# PhotonThingyStick.net
KiCad netlist of a schematic drawn in EAGLE
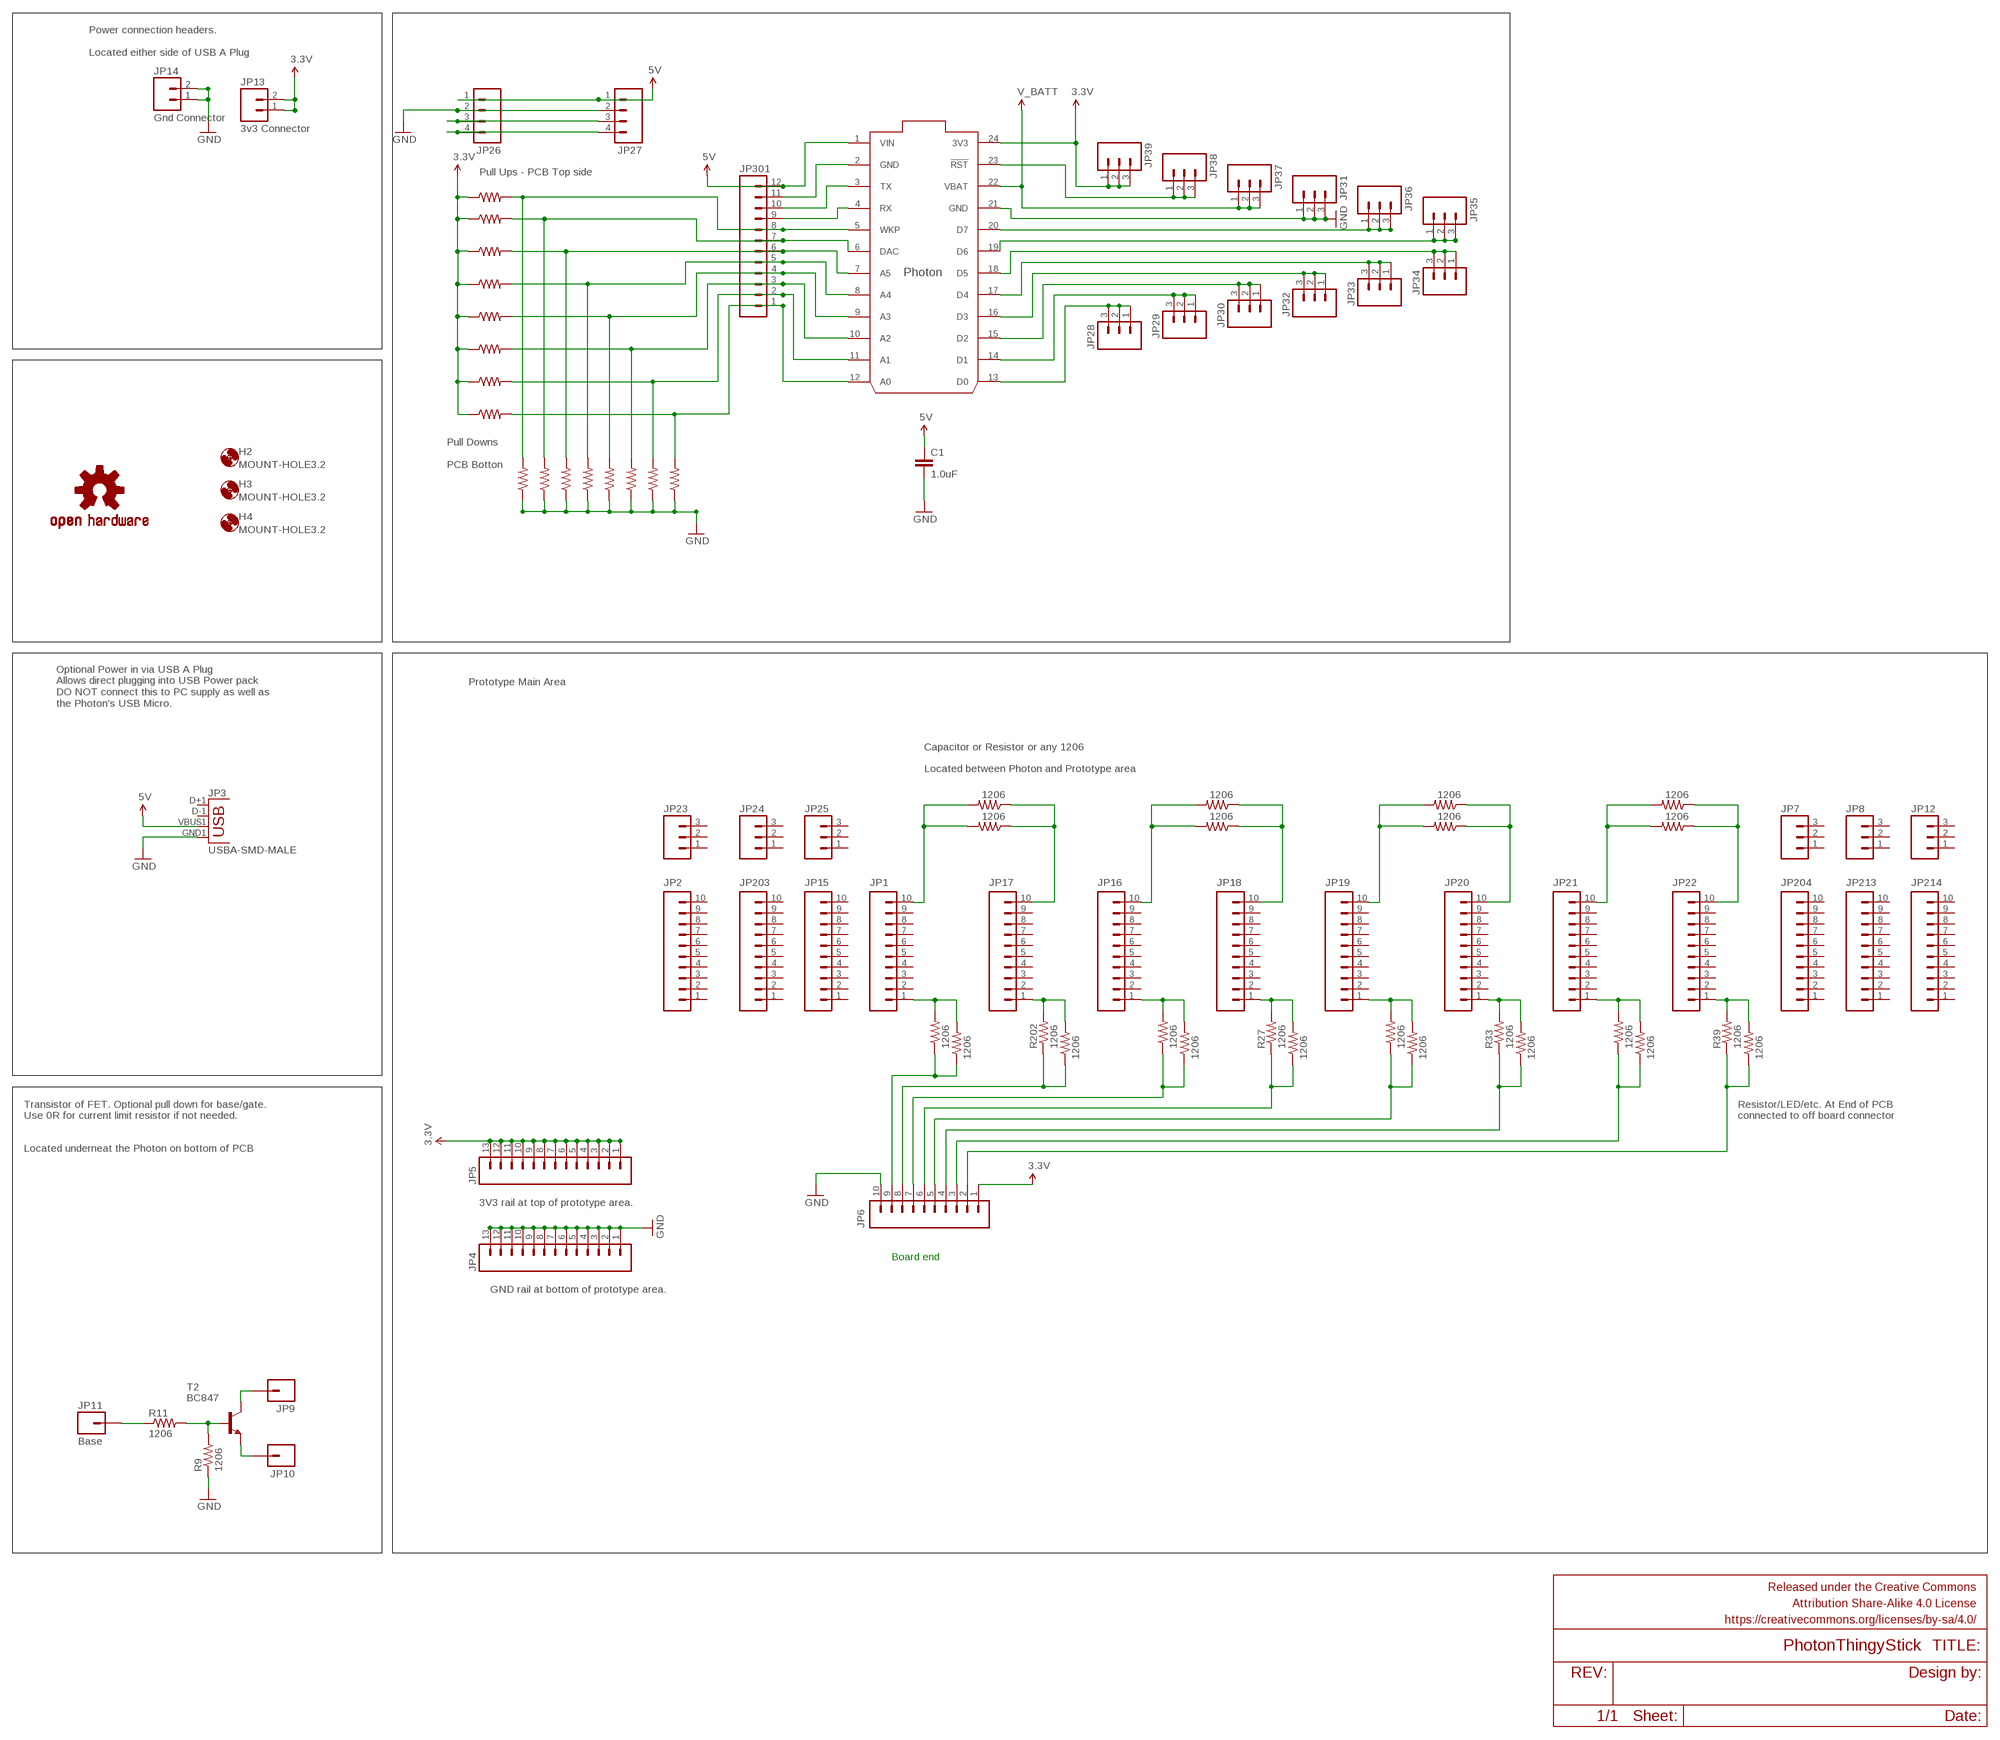
[diagram p0: schematic, sheet 1]

(export (version "E")
  (design (tool "Eeschema 10.0.6"))
  (components
    (comp (ref "C1")
      (value "1.0uF")
      (footprint "eagle-import:0805-CAP")
      (libsource (lib "eagle-import") (part "1.0UF-25V-+80/-20(0805){dblquote}"))
    )
    (comp (ref "FRAME1")
      (value "FRAME-LEDGER")
      (footprint "eagle-import:CREATIVE_COMMONS")
      (libsource (lib "eagle-import") (part "FRAME-LEDGER"))
    )
    (comp (ref "H2")
      (value "MOUNT-HOLE3.2")
      (footprint "eagle-import:3,2")
      (libsource (lib "eagle-import") (part "MOUNT-HOLE3.2"))
    )
    (comp (ref "H3")
      (value "MOUNT-HOLE3.2")
      (footprint "eagle-import:3,2")
      (libsource (lib "eagle-import") (part "MOUNT-HOLE3.2"))
    )
    (comp (ref "H4")
      (value "MOUNT-HOLE3.2")
      (footprint "eagle-import:3,2")
      (libsource (lib "eagle-import") (part "MOUNT-HOLE3.2"))
    )
    (comp (ref "IC1")
      (value "PHOTON_WITH_HEADERS")
      (footprint "eagle-import:PHOTON")
      (libsource (lib "eagle-import") (part "PHOTON_WITH_HEADERS"))
    )
    (comp (ref "JP1")
      (value "M10NO_SILK_PTH_FEMALE")
      (footprint "eagle-import:1X10_NO_SILK")
      (libsource (lib "eagle-import") (part "M10NO_SILK_PTH_FEMALE"))
    )
    (comp (ref "JP2")
      (value "M10NO_SILK_PTH_FEMALE")
      (footprint "eagle-import:1X10_NO_SILK")
      (libsource (lib "eagle-import") (part "M10NO_SILK_PTH_FEMALE"))
    )
    (comp (ref "JP3")
      (value "USBA-SMD-MALE")
      (footprint "eagle-import:USB-A-SMT-MALE")
      (libsource (lib "eagle-import") (part "USBA-SMD-MALE"))
    )
    (comp (ref "JP4")
      (value "M13")
      (footprint "eagle-import:1X13")
      (libsource (lib "eagle-import") (part "M13"))
    )
    (comp (ref "JP5")
      (value "M13")
      (footprint "eagle-import:1X13")
      (libsource (lib "eagle-import") (part "M13"))
    )
    (comp (ref "JP6")
      (value "M10NO_SILK_PTH_FEMALE")
      (footprint "eagle-import:1X10_NO_SILK")
      (libsource (lib "eagle-import") (part "M10NO_SILK_PTH_FEMALE"))
    )
    (comp (ref "JP7")
      (value "M031X03_NO_SILK")
      (footprint "eagle-import:1X03_NO_SILK")
      (libsource (lib "eagle-import") (part "M031X03_NO_SILK"))
    )
    (comp (ref "JP8")
      (value "M031X03_NO_SILK")
      (footprint "eagle-import:1X03_NO_SILK")
      (libsource (lib "eagle-import") (part "M031X03_NO_SILK"))
    )
    (comp (ref "JP9")
      (value "M01PTH")
      (footprint "eagle-import:1X01")
      (libsource (lib "eagle-import") (part "M01PTH"))
    )
    (comp (ref "JP10")
      (value "M01PTH")
      (footprint "eagle-import:1X01")
      (libsource (lib "eagle-import") (part "M01PTH"))
    )
    (comp (ref "JP11")
      (value "Base")
      (footprint "eagle-import:1X01")
      (libsource (lib "eagle-import") (part "M01PTH"))
    )
    (comp (ref "JP12")
      (value "M031X03_NO_SILK")
      (footprint "eagle-import:1X03_NO_SILK")
      (libsource (lib "eagle-import") (part "M031X03_NO_SILK"))
    )
    (comp (ref "JP13")
      (value "3v3 Connector")
      (footprint "eagle-import:1X02")
      (libsource (lib "eagle-import") (part "M02PTH"))
    )
    (comp (ref "JP14")
      (value "Gnd Connector")
      (footprint "eagle-import:1X02")
      (libsource (lib "eagle-import") (part "M02PTH"))
    )
    (comp (ref "JP15")
      (value "M10NO_SILK_PTH_FEMALE")
      (footprint "eagle-import:1X10_NO_SILK")
      (libsource (lib "eagle-import") (part "M10NO_SILK_PTH_FEMALE"))
    )
    (comp (ref "JP16")
      (value "M10NO_SILK_PTH_FEMALE")
      (footprint "eagle-import:1X10_NO_SILK")
      (libsource (lib "eagle-import") (part "M10NO_SILK_PTH_FEMALE"))
    )
    (comp (ref "JP17")
      (value "M10NO_SILK_PTH_FEMALE")
      (footprint "eagle-import:1X10_NO_SILK")
      (libsource (lib "eagle-import") (part "M10NO_SILK_PTH_FEMALE"))
    )
    (comp (ref "JP18")
      (value "M10NO_SILK_PTH_FEMALE")
      (footprint "eagle-import:1X10_NO_SILK")
      (libsource (lib "eagle-import") (part "M10NO_SILK_PTH_FEMALE"))
    )
    (comp (ref "JP19")
      (value "M10NO_SILK_PTH_FEMALE")
      (footprint "eagle-import:1X10_NO_SILK")
      (libsource (lib "eagle-import") (part "M10NO_SILK_PTH_FEMALE"))
    )
    (comp (ref "JP20")
      (value "M10NO_SILK_PTH_FEMALE")
      (footprint "eagle-import:1X10_NO_SILK")
      (libsource (lib "eagle-import") (part "M10NO_SILK_PTH_FEMALE"))
    )
    (comp (ref "JP21")
      (value "M10NO_SILK_PTH_FEMALE")
      (footprint "eagle-import:1X10_NO_SILK")
      (libsource (lib "eagle-import") (part "M10NO_SILK_PTH_FEMALE"))
    )
    (comp (ref "JP22")
      (value "M10NO_SILK_PTH_FEMALE")
      (footprint "eagle-import:1X10_NO_SILK")
      (libsource (lib "eagle-import") (part "M10NO_SILK_PTH_FEMALE"))
    )
    (comp (ref "JP23")
      (value "M031X03_NO_SILK")
      (footprint "eagle-import:1X03_NO_SILK")
      (libsource (lib "eagle-import") (part "M031X03_NO_SILK"))
    )
    (comp (ref "JP24")
      (value "M031X03_NO_SILK")
      (footprint "eagle-import:1X03_NO_SILK")
      (libsource (lib "eagle-import") (part "M031X03_NO_SILK"))
    )
    (comp (ref "JP25")
      (value "M031X03_NO_SILK")
      (footprint "eagle-import:1X03_NO_SILK")
      (libsource (lib "eagle-import") (part "M031X03_NO_SILK"))
    )
    (comp (ref "JP26")
      (value "M041X04_NO_SILK")
      (footprint "eagle-import:1X04_NO_SILK")
      (libsource (lib "eagle-import") (part "M041X04_NO_SILK"))
    )
    (comp (ref "JP27")
      (value "M041X04_NO_SILK")
      (footprint "eagle-import:1X04_NO_SILK")
      (libsource (lib "eagle-import") (part "M041X04_NO_SILK"))
    )
    (comp (ref "JP28")
      (value "M03PTH")
      (footprint "eagle-import:1X03")
      (libsource (lib "eagle-import") (part "M03PTH"))
    )
    (comp (ref "JP29")
      (value "M03PTH")
      (footprint "eagle-import:1X03")
      (libsource (lib "eagle-import") (part "M03PTH"))
    )
    (comp (ref "JP30")
      (value "M03PTH")
      (footprint "eagle-import:1X03")
      (libsource (lib "eagle-import") (part "M03PTH"))
    )
    (comp (ref "JP31")
      (value "M03PTH")
      (footprint "eagle-import:1X03")
      (libsource (lib "eagle-import") (part "M03PTH"))
    )
    (comp (ref "JP32")
      (value "M03PTH")
      (footprint "eagle-import:1X03")
      (libsource (lib "eagle-import") (part "M03PTH"))
    )
    (comp (ref "JP33")
      (value "M03PTH")
      (footprint "eagle-import:1X03")
      (libsource (lib "eagle-import") (part "M03PTH"))
    )
    (comp (ref "JP34")
      (value "M03PTH")
      (footprint "eagle-import:1X03")
      (libsource (lib "eagle-import") (part "M03PTH"))
    )
    (comp (ref "JP35")
      (value "M03PTH")
      (footprint "eagle-import:1X03")
      (libsource (lib "eagle-import") (part "M03PTH"))
    )
    (comp (ref "JP36")
      (value "M03PTH")
      (footprint "eagle-import:1X03")
      (libsource (lib "eagle-import") (part "M03PTH"))
    )
    (comp (ref "JP37")
      (value "M03PTH")
      (footprint "eagle-import:1X03")
      (libsource (lib "eagle-import") (part "M03PTH"))
    )
    (comp (ref "JP38")
      (value "M03PTH")
      (footprint "eagle-import:1X03")
      (libsource (lib "eagle-import") (part "M03PTH"))
    )
    (comp (ref "JP39")
      (value "M03PTH")
      (footprint "eagle-import:1X03")
      (libsource (lib "eagle-import") (part "M03PTH"))
    )
    (comp (ref "JP203")
      (value "M10NO_SILK_PTH_FEMALE")
      (footprint "eagle-import:1X10_NO_SILK")
      (libsource (lib "eagle-import") (part "M10NO_SILK_PTH_FEMALE"))
    )
    (comp (ref "JP204")
      (value "M10NO_SILK_PTH_FEMALE")
      (footprint "eagle-import:1X10_NO_SILK")
      (libsource (lib "eagle-import") (part "M10NO_SILK_PTH_FEMALE"))
    )
    (comp (ref "JP213")
      (value "M10NO_SILK_PTH_FEMALE")
      (footprint "eagle-import:1X10_NO_SILK")
      (libsource (lib "eagle-import") (part "M10NO_SILK_PTH_FEMALE"))
    )
    (comp (ref "JP214")
      (value "M10NO_SILK_PTH_FEMALE")
      (footprint "eagle-import:1X10_NO_SILK")
      (libsource (lib "eagle-import") (part "M10NO_SILK_PTH_FEMALE"))
    )
    (comp (ref "JP301")
      (value "M12PTH")
      (footprint "eagle-import:1X12")
      (libsource (lib "eagle-import") (part "M12PTH"))
    )
    (comp (ref "LOGO1")
      (value "OSHW-LOGOM")
      (footprint "eagle-import:OSHW-LOGO-M")
      (libsource (lib "eagle-import") (part "OSHW-LOGOM"))
    )
    (comp (ref "R1")
      (value "1206")
      (footprint "eagle-import:1206")
      (libsource (lib "eagle-import") (part "SparkFun-Resistors_RESISTOR1206"))
    )
    (comp (ref "R2")
      (value "1206")
      (footprint "eagle-import:1206")
      (libsource (lib "eagle-import") (part "SparkFun-Resistors_RESISTOR1206"))
    )
    (comp (ref "R3")
      (value "1206")
      (footprint "eagle-import:1206")
      (libsource (lib "eagle-import") (part "SparkFun-Resistors_RESISTOR1206"))
    )
    (comp (ref "R4")
      (value "1206")
      (footprint "eagle-import:1206")
      (libsource (lib "eagle-import") (part "SparkFun-Resistors_RESISTOR1206"))
    )
    (comp (ref "R5")
      (value "1206")
      (footprint "eagle-import:1206")
      (libsource (lib "eagle-import") (part "SparkFun-Resistors_RESISTOR1206"))
    )
    (comp (ref "R6")
      (value "1206")
      (footprint "eagle-import:1206")
      (libsource (lib "eagle-import") (part "SparkFun-Resistors_RESISTOR1206"))
    )
    (comp (ref "R7")
      (value "1206")
      (footprint "eagle-import:1206")
      (libsource (lib "eagle-import") (part "SparkFun-Resistors_RESISTOR1206"))
    )
    (comp (ref "R8")
      (value "1206")
      (footprint "eagle-import:1206")
      (libsource (lib "eagle-import") (part "SparkFun-Resistors_RESISTOR1206"))
    )
    (comp (ref "R9")
      (value "1206")
      (footprint "eagle-import:1206")
      (libsource (lib "eagle-import") (part "RESISTOR1206"))
    )
    (comp (ref "R10")
      (value "1206")
      (footprint "eagle-import:1206")
      (libsource (lib "eagle-import") (part "SparkFun-Resistors_RESISTOR1206"))
    )
    (comp (ref "R11")
      (value "1206")
      (footprint "eagle-import:1206")
      (libsource (lib "eagle-import") (part "RESISTOR1206"))
    )
    (comp (ref "R12")
      (value "1206")
      (footprint "eagle-import:1206")
      (libsource (lib "eagle-import") (part "SparkFun-Resistors_RESISTOR1206"))
    )
    (comp (ref "R13")
      (value "1206")
      (footprint "eagle-import:1206")
      (libsource (lib "eagle-import") (part "SparkFun-Resistors_RESISTOR1206"))
    )
    (comp (ref "R14")
      (value "1206")
      (footprint "eagle-import:1206")
      (libsource (lib "eagle-import") (part "SparkFun-Resistors_RESISTOR1206"))
    )
    (comp (ref "R19")
      (value "1206")
      (footprint "eagle-import:1206")
      (libsource (lib "eagle-import") (part "SparkFun-Resistors_RESISTOR1206"))
    )
    (comp (ref "R20")
      (value "1206")
      (footprint "eagle-import:1206")
      (libsource (lib "eagle-import") (part "SparkFun-Resistors_RESISTOR1206"))
    )
    (comp (ref "R21")
      (value "1206")
      (footprint "eagle-import:1206")
      (libsource (lib "eagle-import") (part "SparkFun-Resistors_RESISTOR1206"))
    )
    (comp (ref "R22")
      (value "1206")
      (footprint "eagle-import:1206")
      (libsource (lib "eagle-import") (part "SparkFun-Resistors_RESISTOR1206"))
    )
    (comp (ref "R23")
      (value "1206")
      (footprint "eagle-import:1206")
      (libsource (lib "eagle-import") (part "SparkFun-Resistors_RESISTOR1206"))
    )
    (comp (ref "R24")
      (value "1206")
      (footprint "eagle-import:1206")
      (libsource (lib "eagle-import") (part "SparkFun-Resistors_RESISTOR1206"))
    )
    (comp (ref "R25")
      (value "1206")
      (footprint "eagle-import:1206")
      (libsource (lib "eagle-import") (part "SparkFun-Resistors_RESISTOR1206"))
    )
    (comp (ref "R26")
      (value "1206")
      (footprint "eagle-import:1206")
      (libsource (lib "eagle-import") (part "SparkFun-Resistors_RESISTOR1206"))
    )
    (comp (ref "R27")
      (value "1206")
      (footprint "eagle-import:1206")
      (libsource (lib "eagle-import") (part "SparkFun-Resistors_RESISTOR1206"))
    )
    (comp (ref "R28")
      (value "1206")
      (footprint "eagle-import:1206")
      (libsource (lib "eagle-import") (part "SparkFun-Resistors_RESISTOR1206"))
    )
    (comp (ref "R29")
      (value "1206")
      (footprint "eagle-import:1206")
      (libsource (lib "eagle-import") (part "SparkFun-Resistors_RESISTOR1206"))
    )
    (comp (ref "R30")
      (value "1206")
      (footprint "eagle-import:1206")
      (libsource (lib "eagle-import") (part "SparkFun-Resistors_RESISTOR1206"))
    )
    (comp (ref "R31")
      (value "1206")
      (footprint "eagle-import:1206")
      (libsource (lib "eagle-import") (part "SparkFun-Resistors_RESISTOR1206"))
    )
    (comp (ref "R32")
      (value "1206")
      (footprint "eagle-import:1206")
      (libsource (lib "eagle-import") (part "SparkFun-Resistors_RESISTOR1206"))
    )
    (comp (ref "R33")
      (value "1206")
      (footprint "eagle-import:1206")
      (libsource (lib "eagle-import") (part "SparkFun-Resistors_RESISTOR1206"))
    )
    (comp (ref "R34")
      (value "1206")
      (footprint "eagle-import:1206")
      (libsource (lib "eagle-import") (part "SparkFun-Resistors_RESISTOR1206"))
    )
    (comp (ref "R35")
      (value "1206")
      (footprint "eagle-import:1206")
      (libsource (lib "eagle-import") (part "SparkFun-Resistors_RESISTOR1206"))
    )
    (comp (ref "R36")
      (value "1206")
      (footprint "eagle-import:1206")
      (libsource (lib "eagle-import") (part "SparkFun-Resistors_RESISTOR1206"))
    )
    (comp (ref "R37")
      (value "1206")
      (footprint "eagle-import:1206")
      (libsource (lib "eagle-import") (part "SparkFun-Resistors_RESISTOR1206"))
    )
    (comp (ref "R38")
      (value "1206")
      (footprint "eagle-import:1206")
      (libsource (lib "eagle-import") (part "SparkFun-Resistors_RESISTOR1206"))
    )
    (comp (ref "R39")
      (value "1206")
      (footprint "eagle-import:1206")
      (libsource (lib "eagle-import") (part "SparkFun-Resistors_RESISTOR1206"))
    )
    (comp (ref "R40")
      (value "1206")
      (footprint "eagle-import:1206")
      (libsource (lib "eagle-import") (part "SparkFun-Resistors_RESISTOR1206"))
    )
    (comp (ref "R41")
      (value "1206")
      (footprint "eagle-import:1206")
      (libsource (lib "eagle-import") (part "SparkFun-Resistors_RESISTOR1206"))
    )
    (comp (ref "R42")
      (value "1206")
      (footprint "eagle-import:1206")
      (libsource (lib "eagle-import") (part "SparkFun-Resistors_RESISTOR1206"))
    )
    (comp (ref "R43")
      (value "1206")
      (footprint "eagle-import:1206")
      (libsource (lib "eagle-import") (part "SparkFun-Resistors_RESISTOR1206"))
    )
    (comp (ref "R44")
      (value "1206")
      (footprint "eagle-import:1206")
      (libsource (lib "eagle-import") (part "SparkFun-Resistors_RESISTOR1206"))
    )
    (comp (ref "R201")
      (value "1206")
      (footprint "eagle-import:1206")
      (libsource (lib "eagle-import") (part "SparkFun-Resistors_RESISTOR1206"))
    )
    (comp (ref "R202")
      (value "1206")
      (footprint "eagle-import:1206")
      (libsource (lib "eagle-import") (part "SparkFun-Resistors_RESISTOR1206"))
    )
    (comp (ref "T2")
      (value "BC847")
      (footprint "eagle-import:SOT23")
      (libsource (lib "eagle-import") (part "BC847"))
    )
  )
  (nets
    (net (code "1") (name "/RX") (class "Default")
      (node (ref "IC1") (pin "4") (pinfunction "RX_4") (pintype "bidirectional"))
      (node (ref "JP26") (pin "4") (pinfunction "4_4") (pintype "passive"))
      (node (ref "JP27") (pin "4") (pinfunction "4_4") (pintype "passive"))
      (node (ref "JP301") (pin "9") (pinfunction "9_9") (pintype "passive"))
    )
    (net (code "2") (name "/TX") (class "Default")
      (node (ref "IC1") (pin "3") (pinfunction "TX_3") (pintype "bidirectional"))
      (node (ref "JP26") (pin "3") (pinfunction "3_3") (pintype "passive"))
      (node (ref "JP27") (pin "3") (pinfunction "3_3") (pintype "passive"))
      (node (ref "JP301") (pin "10") (pinfunction "10_10") (pintype "passive"))
    )
    (net (code "3") (name "3.3V") (class "Default")
      (node (ref "IC1") (pin "24") (pinfunction "3V3_24") (pintype "power_in"))
      (node (ref "JP13") (pin "1") (pinfunction "1_1") (pintype "passive"))
      (node (ref "JP13") (pin "2") (pinfunction "2_2") (pintype "passive"))
      (node (ref "JP39") (pin "1") (pinfunction "1_1") (pintype "passive"))
      (node (ref "JP39") (pin "2") (pinfunction "2_2") (pintype "passive"))
      (node (ref "JP39") (pin "3") (pinfunction "3_3") (pintype "passive"))
      (node (ref "JP5") (pin "1") (pinfunction "1_1") (pintype "passive"))
      (node (ref "JP5") (pin "10") (pinfunction "10_10") (pintype "passive"))
      (node (ref "JP5") (pin "11") (pinfunction "11_11") (pintype "passive"))
      (node (ref "JP5") (pin "12") (pinfunction "12_12") (pintype "passive"))
      (node (ref "JP5") (pin "13") (pinfunction "13_13") (pintype "passive"))
      (node (ref "JP5") (pin "2") (pinfunction "2_2") (pintype "passive"))
      (node (ref "JP5") (pin "3") (pinfunction "3_3") (pintype "passive"))
      (node (ref "JP5") (pin "4") (pinfunction "4_4") (pintype "passive"))
      (node (ref "JP5") (pin "5") (pinfunction "5_5") (pintype "passive"))
      (node (ref "JP5") (pin "6") (pinfunction "6_6") (pintype "passive"))
      (node (ref "JP5") (pin "7") (pinfunction "7_7") (pintype "passive"))
      (node (ref "JP5") (pin "8") (pinfunction "8_8") (pintype "passive"))
      (node (ref "JP5") (pin "9") (pinfunction "9_9") (pintype "passive"))
      (node (ref "JP6") (pin "1") (pinfunction "1_1") (pintype "passive"))
      (node (ref "R1") (pin "1") (pinfunction "1_1") (pintype "passive"))
      (node (ref "R12") (pin "1") (pinfunction "1_1") (pintype "passive"))
      (node (ref "R2") (pin "1") (pinfunction "1_1") (pintype "passive"))
      (node (ref "R3") (pin "1") (pinfunction "1_1") (pintype "passive"))
      (node (ref "R4") (pin "1") (pinfunction "1_1") (pintype "passive"))
      (node (ref "R5") (pin "1") (pinfunction "1_1") (pintype "passive"))
      (node (ref "R6") (pin "1") (pinfunction "1_1") (pintype "passive"))
      (node (ref "R7") (pin "1") (pinfunction "1_1") (pintype "passive"))
    )
    (net (code "4") (name "5V") (class "Default")
      (node (ref "C1") (pin "1") (pinfunction "1_1") (pintype "passive"))
      (node (ref "IC1") (pin "1") (pinfunction "VIN_1") (pintype "power_in"))
      (node (ref "JP26") (pin "1") (pinfunction "1_1") (pintype "passive"))
      (node (ref "JP27") (pin "1") (pinfunction "1_1") (pintype "passive"))
      (node (ref "JP3") (pin "VBUS1") (pinfunction "VBUS_VBUS1") (pintype "bidirectional"))
      (node (ref "JP301") (pin "12") (pinfunction "12_12") (pintype "passive"))
    )
    (net (code "5") (name "GND") (class "Default")
      (node (ref "C1") (pin "2") (pinfunction "2_2") (pintype "passive"))
      (node (ref "IC1") (pin "2") (pinfunction "GND_2") (pintype "power_in"))
      (node (ref "IC1") (pin "21") (pinfunction "GND_21") (pintype "power_in"))
      (node (ref "JP14") (pin "1") (pinfunction "1_1") (pintype "passive"))
      (node (ref "JP14") (pin "2") (pinfunction "2_2") (pintype "passive"))
      (node (ref "JP26") (pin "2") (pinfunction "2_2") (pintype "passive"))
      (node (ref "JP27") (pin "2") (pinfunction "2_2") (pintype "passive"))
      (node (ref "JP3") (pin "GND1") (pinfunction "GND_GND1") (pintype "bidirectional"))
      (node (ref "JP301") (pin "11") (pinfunction "11_11") (pintype "passive"))
      (node (ref "JP31") (pin "1") (pinfunction "1_1") (pintype "passive"))
      (node (ref "JP31") (pin "2") (pinfunction "2_2") (pintype "passive"))
      (node (ref "JP31") (pin "3") (pinfunction "3_3") (pintype "passive"))
      (node (ref "JP4") (pin "1") (pinfunction "1_1") (pintype "passive"))
      (node (ref "JP4") (pin "10") (pinfunction "10_10") (pintype "passive"))
      (node (ref "JP4") (pin "11") (pinfunction "11_11") (pintype "passive"))
      (node (ref "JP4") (pin "12") (pinfunction "12_12") (pintype "passive"))
      (node (ref "JP4") (pin "13") (pinfunction "13_13") (pintype "passive"))
      (node (ref "JP4") (pin "2") (pinfunction "2_2") (pintype "passive"))
      (node (ref "JP4") (pin "3") (pinfunction "3_3") (pintype "passive"))
      (node (ref "JP4") (pin "4") (pinfunction "4_4") (pintype "passive"))
      (node (ref "JP4") (pin "5") (pinfunction "5_5") (pintype "passive"))
      (node (ref "JP4") (pin "6") (pinfunction "6_6") (pintype "passive"))
      (node (ref "JP4") (pin "7") (pinfunction "7_7") (pintype "passive"))
      (node (ref "JP4") (pin "8") (pinfunction "8_8") (pintype "passive"))
      (node (ref "JP4") (pin "9") (pinfunction "9_9") (pintype "passive"))
      (node (ref "JP6") (pin "10") (pinfunction "10_10") (pintype "passive"))
      (node (ref "R10") (pin "1") (pinfunction "1_1") (pintype "passive"))
      (node (ref "R13") (pin "1") (pinfunction "1_1") (pintype "passive"))
      (node (ref "R14") (pin "1") (pinfunction "1_1") (pintype "passive"))
      (node (ref "R19") (pin "1") (pinfunction "1_1") (pintype "passive"))
      (node (ref "R20") (pin "1") (pinfunction "1_1") (pintype "passive"))
      (node (ref "R21") (pin "1") (pinfunction "1_1") (pintype "passive"))
      (node (ref "R22") (pin "1") (pinfunction "1_1") (pintype "passive"))
      (node (ref "R8") (pin "1") (pinfunction "1_1") (pintype "passive"))
      (node (ref "R9") (pin "1") (pinfunction "1_1") (pintype "passive"))
    )
    (net (code "6") (name "Net-(IC1-A0)") (class "Default")
      (node (ref "IC1") (pin "12") (pinfunction "A0_12") (pintype "bidirectional"))
      (node (ref "JP301") (pin "1") (pinfunction "1_1") (pintype "passive"))
      (node (ref "R22") (pin "2") (pinfunction "2_2") (pintype "passive"))
      (node (ref "R7") (pin "2") (pinfunction "2_2") (pintype "passive"))
    )
    (net (code "7") (name "Net-(IC1-A1)") (class "Default")
      (node (ref "IC1") (pin "11") (pinfunction "A1_11") (pintype "bidirectional"))
      (node (ref "JP301") (pin "2") (pinfunction "2_2") (pintype "passive"))
      (node (ref "R21") (pin "2") (pinfunction "2_2") (pintype "passive"))
      (node (ref "R6") (pin "2") (pinfunction "2_2") (pintype "passive"))
    )
    (net (code "8") (name "Net-(IC1-A2)") (class "Default")
      (node (ref "IC1") (pin "10") (pinfunction "A2_10") (pintype "bidirectional"))
      (node (ref "JP301") (pin "3") (pinfunction "3_3") (pintype "passive"))
      (node (ref "R20") (pin "2") (pinfunction "2_2") (pintype "passive"))
      (node (ref "R4") (pin "2") (pinfunction "2_2") (pintype "passive"))
    )
    (net (code "9") (name "Net-(IC1-A3)") (class "Default")
      (node (ref "IC1") (pin "9") (pinfunction "A3_9") (pintype "bidirectional"))
      (node (ref "JP301") (pin "4") (pinfunction "4_4") (pintype "passive"))
      (node (ref "R19") (pin "2") (pinfunction "2_2") (pintype "passive"))
      (node (ref "R3") (pin "2") (pinfunction "2_2") (pintype "passive"))
    )
    (net (code "10") (name "Net-(IC1-A4)") (class "Default")
      (node (ref "IC1") (pin "8") (pinfunction "A4_8") (pintype "bidirectional"))
      (node (ref "JP301") (pin "5") (pinfunction "5_5") (pintype "passive"))
      (node (ref "R14") (pin "2") (pinfunction "2_2") (pintype "passive"))
      (node (ref "R2") (pin "2") (pinfunction "2_2") (pintype "passive"))
    )
    (net (code "11") (name "Net-(IC1-A5)") (class "Default")
      (node (ref "IC1") (pin "7") (pinfunction "A5_7") (pintype "bidirectional"))
      (node (ref "JP301") (pin "6") (pinfunction "6_6") (pintype "passive"))
      (node (ref "R1") (pin "2") (pinfunction "2_2") (pintype "passive"))
      (node (ref "R13") (pin "2") (pinfunction "2_2") (pintype "passive"))
    )
    (net (code "12") (name "Net-(IC1-D0)") (class "Default")
      (node (ref "IC1") (pin "13") (pinfunction "D0_13") (pintype "bidirectional"))
      (node (ref "JP28") (pin "1") (pinfunction "1_1") (pintype "passive"))
      (node (ref "JP28") (pin "2") (pinfunction "2_2") (pintype "passive"))
      (node (ref "JP28") (pin "3") (pinfunction "3_3") (pintype "passive"))
    )
    (net (code "13") (name "Net-(IC1-D1)") (class "Default")
      (node (ref "IC1") (pin "14") (pinfunction "D1_14") (pintype "bidirectional"))
      (node (ref "JP29") (pin "1") (pinfunction "1_1") (pintype "passive"))
      (node (ref "JP29") (pin "2") (pinfunction "2_2") (pintype "passive"))
      (node (ref "JP29") (pin "3") (pinfunction "3_3") (pintype "passive"))
    )
    (net (code "14") (name "Net-(IC1-D2)") (class "Default")
      (node (ref "IC1") (pin "15") (pinfunction "D2_15") (pintype "bidirectional"))
      (node (ref "JP30") (pin "1") (pinfunction "1_1") (pintype "passive"))
      (node (ref "JP30") (pin "2") (pinfunction "2_2") (pintype "passive"))
      (node (ref "JP30") (pin "3") (pinfunction "3_3") (pintype "passive"))
    )
    (net (code "15") (name "Net-(IC1-D3)") (class "Default")
      (node (ref "IC1") (pin "16") (pinfunction "D3_16") (pintype "bidirectional"))
      (node (ref "JP32") (pin "1") (pinfunction "1_1") (pintype "passive"))
      (node (ref "JP32") (pin "2") (pinfunction "2_2") (pintype "passive"))
      (node (ref "JP32") (pin "3") (pinfunction "3_3") (pintype "passive"))
    )
    (net (code "16") (name "Net-(IC1-D4)") (class "Default")
      (node (ref "IC1") (pin "17") (pinfunction "D4_17") (pintype "bidirectional"))
      (node (ref "JP33") (pin "1") (pinfunction "1_1") (pintype "passive"))
      (node (ref "JP33") (pin "2") (pinfunction "2_2") (pintype "passive"))
      (node (ref "JP33") (pin "3") (pinfunction "3_3") (pintype "passive"))
    )
    (net (code "17") (name "Net-(IC1-D5)") (class "Default")
      (node (ref "IC1") (pin "18") (pinfunction "D5_18") (pintype "bidirectional"))
      (node (ref "JP34") (pin "1") (pinfunction "1_1") (pintype "passive"))
      (node (ref "JP34") (pin "2") (pinfunction "2_2") (pintype "passive"))
      (node (ref "JP34") (pin "3") (pinfunction "3_3") (pintype "passive"))
    )
    (net (code "18") (name "Net-(IC1-D6)") (class "Default")
      (node (ref "IC1") (pin "19") (pinfunction "D6_19") (pintype "bidirectional"))
      (node (ref "JP35") (pin "1") (pinfunction "1_1") (pintype "passive"))
      (node (ref "JP35") (pin "2") (pinfunction "2_2") (pintype "passive"))
      (node (ref "JP35") (pin "3") (pinfunction "3_3") (pintype "passive"))
    )
    (net (code "19") (name "Net-(IC1-D7)") (class "Default")
      (node (ref "IC1") (pin "20") (pinfunction "D7_20") (pintype "bidirectional"))
      (node (ref "JP36") (pin "1") (pinfunction "1_1") (pintype "passive"))
      (node (ref "JP36") (pin "2") (pinfunction "2_2") (pintype "passive"))
      (node (ref "JP36") (pin "3") (pinfunction "3_3") (pintype "passive"))
    )
    (net (code "20") (name "Net-(IC1-DAC)") (class "Default")
      (node (ref "IC1") (pin "6") (pinfunction "DAC_6") (pintype "bidirectional"))
      (node (ref "JP301") (pin "7") (pinfunction "7_7") (pintype "passive"))
      (node (ref "R10") (pin "2") (pinfunction "2_2") (pintype "passive"))
      (node (ref "R5") (pin "2") (pinfunction "2_2") (pintype "passive"))
    )
    (net (code "21") (name "Net-(IC1-WKP)") (class "Default")
      (node (ref "IC1") (pin "5") (pinfunction "WKP_5") (pintype "bidirectional"))
      (node (ref "JP301") (pin "8") (pinfunction "8_8") (pintype "passive"))
      (node (ref "R12") (pin "2") (pinfunction "2_2") (pintype "passive"))
      (node (ref "R8") (pin "2") (pinfunction "2_2") (pintype "passive"))
    )
    (net (code "22") (name "Net-(IC1-~{RST})") (class "Default")
      (node (ref "IC1") (pin "23") (pinfunction "~{RST}_23") (pintype "bidirectional"))
      (node (ref "JP38") (pin "1") (pinfunction "1_1") (pintype "passive"))
      (node (ref "JP38") (pin "2") (pinfunction "2_2") (pintype "passive"))
      (node (ref "JP38") (pin "3") (pinfunction "3_3") (pintype "passive"))
    )
    (net (code "23") (name "Net-(JP1-Pad1)") (class "Default")
      (node (ref "JP1") (pin "1") (pinfunction "1_1") (pintype "passive"))
      (node (ref "R201") (pin "2") (pinfunction "2_2") (pintype "passive"))
      (node (ref "R23") (pin "2") (pinfunction "2_2") (pintype "passive"))
    )
    (net (code "24") (name "Net-(JP1-Pad10)") (class "Default")
      (node (ref "JP1") (pin "10") (pinfunction "10_10") (pintype "passive"))
      (node (ref "R24") (pin "2") (pinfunction "2_2") (pintype "passive"))
      (node (ref "R25") (pin "2") (pinfunction "2_2") (pintype "passive"))
    )
    (net (code "25") (name "Net-(JP6-Pad2)") (class "Default")
      (node (ref "JP6") (pin "2") (pinfunction "2_2") (pintype "passive"))
      (node (ref "R39") (pin "1") (pinfunction "1_1") (pintype "passive"))
      (node (ref "R44") (pin "1") (pinfunction "1_1") (pintype "passive"))
    )
    (net (code "26") (name "Net-(JP6-Pad3)") (class "Default")
      (node (ref "JP6") (pin "3") (pinfunction "3_3") (pintype "passive"))
      (node (ref "R40") (pin "1") (pinfunction "1_1") (pintype "passive"))
      (node (ref "R41") (pin "1") (pinfunction "1_1") (pintype "passive"))
    )
    (net (code "27") (name "Net-(JP6-Pad4)") (class "Default")
      (node (ref "JP6") (pin "4") (pinfunction "4_4") (pintype "passive"))
      (node (ref "R33") (pin "1") (pinfunction "1_1") (pintype "passive"))
      (node (ref "R38") (pin "1") (pinfunction "1_1") (pintype "passive"))
    )
    (net (code "28") (name "Net-(JP6-Pad5)") (class "Default")
      (node (ref "JP6") (pin "5") (pinfunction "5_5") (pintype "passive"))
      (node (ref "R34") (pin "1") (pinfunction "1_1") (pintype "passive"))
      (node (ref "R35") (pin "1") (pinfunction "1_1") (pintype "passive"))
    )
    (net (code "29") (name "Net-(JP6-Pad6)") (class "Default")
      (node (ref "JP6") (pin "6") (pinfunction "6_6") (pintype "passive"))
      (node (ref "R27") (pin "1") (pinfunction "1_1") (pintype "passive"))
      (node (ref "R32") (pin "1") (pinfunction "1_1") (pintype "passive"))
    )
    (net (code "30") (name "Net-(JP6-Pad7)") (class "Default")
      (node (ref "JP6") (pin "7") (pinfunction "7_7") (pintype "passive"))
      (node (ref "R28") (pin "1") (pinfunction "1_1") (pintype "passive"))
      (node (ref "R29") (pin "1") (pinfunction "1_1") (pintype "passive"))
    )
    (net (code "31") (name "Net-(JP6-Pad8)") (class "Default")
      (node (ref "JP6") (pin "8") (pinfunction "8_8") (pintype "passive"))
      (node (ref "R202") (pin "1") (pinfunction "1_1") (pintype "passive"))
      (node (ref "R26") (pin "1") (pinfunction "1_1") (pintype "passive"))
    )
    (net (code "32") (name "Net-(JP6-Pad9)") (class "Default")
      (node (ref "JP6") (pin "9") (pinfunction "9_9") (pintype "passive"))
      (node (ref "R201") (pin "1") (pinfunction "1_1") (pintype "passive"))
      (node (ref "R23") (pin "1") (pinfunction "1_1") (pintype "passive"))
    )
    (net (code "33") (name "Net-(JP11-Pad1)") (class "Default")
      (node (ref "JP11") (pin "1") (pinfunction "1_1") (pintype "passive"))
      (node (ref "R11") (pin "1") (pinfunction "1_1") (pintype "passive"))
    )
    (net (code "34") (name "Net-(JP16-Pad1)") (class "Default")
      (node (ref "JP16") (pin "1") (pinfunction "1_1") (pintype "passive"))
      (node (ref "R28") (pin "2") (pinfunction "2_2") (pintype "passive"))
      (node (ref "R29") (pin "2") (pinfunction "2_2") (pintype "passive"))
    )
    (net (code "35") (name "Net-(JP16-Pad10)") (class "Default")
      (node (ref "JP16") (pin "10") (pinfunction "10_10") (pintype "passive"))
      (node (ref "R30") (pin "2") (pinfunction "2_2") (pintype "passive"))
      (node (ref "R31") (pin "2") (pinfunction "2_2") (pintype "passive"))
    )
    (net (code "36") (name "Net-(JP17-Pad1)") (class "Default")
      (node (ref "JP17") (pin "1") (pinfunction "1_1") (pintype "passive"))
      (node (ref "R202") (pin "2") (pinfunction "2_2") (pintype "passive"))
      (node (ref "R26") (pin "2") (pinfunction "2_2") (pintype "passive"))
    )
    (net (code "37") (name "Net-(JP17-Pad10)") (class "Default")
      (node (ref "JP17") (pin "10") (pinfunction "10_10") (pintype "passive"))
      (node (ref "R24") (pin "1") (pinfunction "1_1") (pintype "passive"))
      (node (ref "R25") (pin "1") (pinfunction "1_1") (pintype "passive"))
    )
    (net (code "38") (name "Net-(JP18-Pad1)") (class "Default")
      (node (ref "JP18") (pin "1") (pinfunction "1_1") (pintype "passive"))
      (node (ref "R27") (pin "2") (pinfunction "2_2") (pintype "passive"))
      (node (ref "R32") (pin "2") (pinfunction "2_2") (pintype "passive"))
    )
    (net (code "39") (name "Net-(JP18-Pad10)") (class "Default")
      (node (ref "JP18") (pin "10") (pinfunction "10_10") (pintype "passive"))
      (node (ref "R30") (pin "1") (pinfunction "1_1") (pintype "passive"))
      (node (ref "R31") (pin "1") (pinfunction "1_1") (pintype "passive"))
    )
    (net (code "40") (name "Net-(JP19-Pad1)") (class "Default")
      (node (ref "JP19") (pin "1") (pinfunction "1_1") (pintype "passive"))
      (node (ref "R34") (pin "2") (pinfunction "2_2") (pintype "passive"))
      (node (ref "R35") (pin "2") (pinfunction "2_2") (pintype "passive"))
    )
    (net (code "41") (name "Net-(JP19-Pad10)") (class "Default")
      (node (ref "JP19") (pin "10") (pinfunction "10_10") (pintype "passive"))
      (node (ref "R36") (pin "2") (pinfunction "2_2") (pintype "passive"))
      (node (ref "R37") (pin "2") (pinfunction "2_2") (pintype "passive"))
    )
    (net (code "42") (name "Net-(JP20-Pad1)") (class "Default")
      (node (ref "JP20") (pin "1") (pinfunction "1_1") (pintype "passive"))
      (node (ref "R33") (pin "2") (pinfunction "2_2") (pintype "passive"))
      (node (ref "R38") (pin "2") (pinfunction "2_2") (pintype "passive"))
    )
    (net (code "43") (name "Net-(JP20-Pad10)") (class "Default")
      (node (ref "JP20") (pin "10") (pinfunction "10_10") (pintype "passive"))
      (node (ref "R36") (pin "1") (pinfunction "1_1") (pintype "passive"))
      (node (ref "R37") (pin "1") (pinfunction "1_1") (pintype "passive"))
    )
    (net (code "44") (name "Net-(JP21-Pad1)") (class "Default")
      (node (ref "JP21") (pin "1") (pinfunction "1_1") (pintype "passive"))
      (node (ref "R40") (pin "2") (pinfunction "2_2") (pintype "passive"))
      (node (ref "R41") (pin "2") (pinfunction "2_2") (pintype "passive"))
    )
    (net (code "45") (name "Net-(JP21-Pad10)") (class "Default")
      (node (ref "JP21") (pin "10") (pinfunction "10_10") (pintype "passive"))
      (node (ref "R42") (pin "2") (pinfunction "2_2") (pintype "passive"))
      (node (ref "R43") (pin "2") (pinfunction "2_2") (pintype "passive"))
    )
    (net (code "46") (name "Net-(JP22-Pad1)") (class "Default")
      (node (ref "JP22") (pin "1") (pinfunction "1_1") (pintype "passive"))
      (node (ref "R39") (pin "2") (pinfunction "2_2") (pintype "passive"))
      (node (ref "R44") (pin "2") (pinfunction "2_2") (pintype "passive"))
    )
    (net (code "47") (name "Net-(JP22-Pad10)") (class "Default")
      (node (ref "JP22") (pin "10") (pinfunction "10_10") (pintype "passive"))
      (node (ref "R42") (pin "1") (pinfunction "1_1") (pintype "passive"))
      (node (ref "R43") (pin "1") (pinfunction "1_1") (pintype "passive"))
    )
    (net (code "48") (name "Net-(T2-B)") (class "Default")
      (node (ref "R11") (pin "2") (pinfunction "2_2") (pintype "passive"))
      (node (ref "R9") (pin "2") (pinfunction "2_2") (pintype "passive"))
      (node (ref "T2") (pin "1") (pinfunction "B_1") (pintype "passive"))
    )
    (net (code "49") (name "Net-(T2-C)") (class "Default")
      (node (ref "JP9") (pin "1") (pinfunction "1_1") (pintype "passive"))
      (node (ref "T2") (pin "3") (pinfunction "C_3") (pintype "passive"))
    )
    (net (code "50") (name "Net-(T2-E)") (class "Default")
      (node (ref "JP10") (pin "1") (pinfunction "1_1") (pintype "passive"))
      (node (ref "T2") (pin "2") (pinfunction "E_2") (pintype "passive"))
    )
    (net (code "51") (name "V_BATT") (class "Default")
      (node (ref "IC1") (pin "22") (pinfunction "VBAT_22") (pintype "power_in"))
      (node (ref "JP37") (pin "1") (pinfunction "1_1") (pintype "passive"))
      (node (ref "JP37") (pin "2") (pinfunction "2_2") (pintype "passive"))
      (node (ref "JP37") (pin "3") (pinfunction "3_3") (pintype "passive"))
    )
    (net (code "52") (name "unconnected-(JP1-Pad2)") (class "Default")
      (node (ref "JP1") (pin "2") (pinfunction "2_2") (pintype "passive"))
    )
    (net (code "53") (name "unconnected-(JP1-Pad3)") (class "Default")
      (node (ref "JP1") (pin "3") (pinfunction "3_3") (pintype "passive"))
    )
    (net (code "54") (name "unconnected-(JP1-Pad4)") (class "Default")
      (node (ref "JP1") (pin "4") (pinfunction "4_4") (pintype "passive"))
    )
    (net (code "55") (name "unconnected-(JP1-Pad5)") (class "Default")
      (node (ref "JP1") (pin "5") (pinfunction "5_5") (pintype "passive"))
    )
    (net (code "56") (name "unconnected-(JP1-Pad6)") (class "Default")
      (node (ref "JP1") (pin "6") (pinfunction "6_6") (pintype "passive"))
    )
    (net (code "57") (name "unconnected-(JP1-Pad7)") (class "Default")
      (node (ref "JP1") (pin "7") (pinfunction "7_7") (pintype "passive"))
    )
    (net (code "58") (name "unconnected-(JP1-Pad8)") (class "Default")
      (node (ref "JP1") (pin "8") (pinfunction "8_8") (pintype "passive"))
    )
    (net (code "59") (name "unconnected-(JP1-Pad9)") (class "Default")
      (node (ref "JP1") (pin "9") (pinfunction "9_9") (pintype "passive"))
    )
    (net (code "60") (name "unconnected-(JP2-Pad1)") (class "Default")
      (node (ref "JP2") (pin "1") (pinfunction "1_1") (pintype "passive"))
    )
    (net (code "61") (name "unconnected-(JP2-Pad2)") (class "Default")
      (node (ref "JP2") (pin "2") (pinfunction "2_2") (pintype "passive"))
    )
    (net (code "62") (name "unconnected-(JP2-Pad3)") (class "Default")
      (node (ref "JP2") (pin "3") (pinfunction "3_3") (pintype "passive"))
    )
    (net (code "63") (name "unconnected-(JP2-Pad4)") (class "Default")
      (node (ref "JP2") (pin "4") (pinfunction "4_4") (pintype "passive"))
    )
    (net (code "64") (name "unconnected-(JP2-Pad5)") (class "Default")
      (node (ref "JP2") (pin "5") (pinfunction "5_5") (pintype "passive"))
    )
    (net (code "65") (name "unconnected-(JP2-Pad6)") (class "Default")
      (node (ref "JP2") (pin "6") (pinfunction "6_6") (pintype "passive"))
    )
    (net (code "66") (name "unconnected-(JP2-Pad7)") (class "Default")
      (node (ref "JP2") (pin "7") (pinfunction "7_7") (pintype "passive"))
    )
    (net (code "67") (name "unconnected-(JP2-Pad8)") (class "Default")
      (node (ref "JP2") (pin "8") (pinfunction "8_8") (pintype "passive"))
    )
    (net (code "68") (name "unconnected-(JP2-Pad9)") (class "Default")
      (node (ref "JP2") (pin "9") (pinfunction "9_9") (pintype "passive"))
    )
    (net (code "69") (name "unconnected-(JP2-Pad10)") (class "Default")
      (node (ref "JP2") (pin "10") (pinfunction "10_10") (pintype "passive"))
    )
    (net (code "70") (name "unconnected-(JP3-D+-PadD+1)") (class "Default")
      (node (ref "JP3") (pin "D+1") (pinfunction "D+_D+1") (pintype "bidirectional"))
    )
    (net (code "71") (name "unconnected-(JP3-D--PadD-1)") (class "Default")
      (node (ref "JP3") (pin "D-1") (pinfunction "D-_D-1") (pintype "bidirectional"))
    )
    (net (code "72") (name "unconnected-(JP7-Pad1)") (class "Default")
      (node (ref "JP7") (pin "1") (pinfunction "1_1") (pintype "passive"))
    )
    (net (code "73") (name "unconnected-(JP7-Pad2)") (class "Default")
      (node (ref "JP7") (pin "2") (pinfunction "2_2") (pintype "passive"))
    )
    (net (code "74") (name "unconnected-(JP7-Pad3)") (class "Default")
      (node (ref "JP7") (pin "3") (pinfunction "3_3") (pintype "passive"))
    )
    (net (code "75") (name "unconnected-(JP8-Pad1)") (class "Default")
      (node (ref "JP8") (pin "1") (pinfunction "1_1") (pintype "passive"))
    )
    (net (code "76") (name "unconnected-(JP8-Pad2)") (class "Default")
      (node (ref "JP8") (pin "2") (pinfunction "2_2") (pintype "passive"))
    )
    (net (code "77") (name "unconnected-(JP8-Pad3)") (class "Default")
      (node (ref "JP8") (pin "3") (pinfunction "3_3") (pintype "passive"))
    )
    (net (code "78") (name "unconnected-(JP12-Pad1)") (class "Default")
      (node (ref "JP12") (pin "1") (pinfunction "1_1") (pintype "passive"))
    )
    (net (code "79") (name "unconnected-(JP12-Pad2)") (class "Default")
      (node (ref "JP12") (pin "2") (pinfunction "2_2") (pintype "passive"))
    )
    (net (code "80") (name "unconnected-(JP12-Pad3)") (class "Default")
      (node (ref "JP12") (pin "3") (pinfunction "3_3") (pintype "passive"))
    )
    (net (code "81") (name "unconnected-(JP15-Pad1)") (class "Default")
      (node (ref "JP15") (pin "1") (pinfunction "1_1") (pintype "passive"))
    )
    (net (code "82") (name "unconnected-(JP15-Pad2)") (class "Default")
      (node (ref "JP15") (pin "2") (pinfunction "2_2") (pintype "passive"))
    )
    (net (code "83") (name "unconnected-(JP15-Pad3)") (class "Default")
      (node (ref "JP15") (pin "3") (pinfunction "3_3") (pintype "passive"))
    )
    (net (code "84") (name "unconnected-(JP15-Pad4)") (class "Default")
      (node (ref "JP15") (pin "4") (pinfunction "4_4") (pintype "passive"))
    )
    (net (code "85") (name "unconnected-(JP15-Pad5)") (class "Default")
      (node (ref "JP15") (pin "5") (pinfunction "5_5") (pintype "passive"))
    )
    (net (code "86") (name "unconnected-(JP15-Pad6)") (class "Default")
      (node (ref "JP15") (pin "6") (pinfunction "6_6") (pintype "passive"))
    )
    (net (code "87") (name "unconnected-(JP15-Pad7)") (class "Default")
      (node (ref "JP15") (pin "7") (pinfunction "7_7") (pintype "passive"))
    )
    (net (code "88") (name "unconnected-(JP15-Pad8)") (class "Default")
      (node (ref "JP15") (pin "8") (pinfunction "8_8") (pintype "passive"))
    )
    (net (code "89") (name "unconnected-(JP15-Pad9)") (class "Default")
      (node (ref "JP15") (pin "9") (pinfunction "9_9") (pintype "passive"))
    )
    (net (code "90") (name "unconnected-(JP15-Pad10)") (class "Default")
      (node (ref "JP15") (pin "10") (pinfunction "10_10") (pintype "passive"))
    )
    (net (code "91") (name "unconnected-(JP16-Pad2)") (class "Default")
      (node (ref "JP16") (pin "2") (pinfunction "2_2") (pintype "passive"))
    )
    (net (code "92") (name "unconnected-(JP16-Pad3)") (class "Default")
      (node (ref "JP16") (pin "3") (pinfunction "3_3") (pintype "passive"))
    )
    (net (code "93") (name "unconnected-(JP16-Pad4)") (class "Default")
      (node (ref "JP16") (pin "4") (pinfunction "4_4") (pintype "passive"))
    )
    (net (code "94") (name "unconnected-(JP16-Pad5)") (class "Default")
      (node (ref "JP16") (pin "5") (pinfunction "5_5") (pintype "passive"))
    )
    (net (code "95") (name "unconnected-(JP16-Pad6)") (class "Default")
      (node (ref "JP16") (pin "6") (pinfunction "6_6") (pintype "passive"))
    )
    (net (code "96") (name "unconnected-(JP16-Pad7)") (class "Default")
      (node (ref "JP16") (pin "7") (pinfunction "7_7") (pintype "passive"))
    )
    (net (code "97") (name "unconnected-(JP16-Pad8)") (class "Default")
      (node (ref "JP16") (pin "8") (pinfunction "8_8") (pintype "passive"))
    )
    (net (code "98") (name "unconnected-(JP16-Pad9)") (class "Default")
      (node (ref "JP16") (pin "9") (pinfunction "9_9") (pintype "passive"))
    )
    (net (code "99") (name "unconnected-(JP17-Pad2)") (class "Default")
      (node (ref "JP17") (pin "2") (pinfunction "2_2") (pintype "passive"))
    )
    (net (code "100") (name "unconnected-(JP17-Pad3)") (class "Default")
      (node (ref "JP17") (pin "3") (pinfunction "3_3") (pintype "passive"))
    )
    (net (code "101") (name "unconnected-(JP17-Pad4)") (class "Default")
      (node (ref "JP17") (pin "4") (pinfunction "4_4") (pintype "passive"))
    )
    (net (code "102") (name "unconnected-(JP17-Pad5)") (class "Default")
      (node (ref "JP17") (pin "5") (pinfunction "5_5") (pintype "passive"))
    )
    (net (code "103") (name "unconnected-(JP17-Pad6)") (class "Default")
      (node (ref "JP17") (pin "6") (pinfunction "6_6") (pintype "passive"))
    )
    (net (code "104") (name "unconnected-(JP17-Pad7)") (class "Default")
      (node (ref "JP17") (pin "7") (pinfunction "7_7") (pintype "passive"))
    )
    (net (code "105") (name "unconnected-(JP17-Pad8)") (class "Default")
      (node (ref "JP17") (pin "8") (pinfunction "8_8") (pintype "passive"))
    )
    (net (code "106") (name "unconnected-(JP17-Pad9)") (class "Default")
      (node (ref "JP17") (pin "9") (pinfunction "9_9") (pintype "passive"))
    )
    (net (code "107") (name "unconnected-(JP18-Pad2)") (class "Default")
      (node (ref "JP18") (pin "2") (pinfunction "2_2") (pintype "passive"))
    )
    (net (code "108") (name "unconnected-(JP18-Pad3)") (class "Default")
      (node (ref "JP18") (pin "3") (pinfunction "3_3") (pintype "passive"))
    )
    (net (code "109") (name "unconnected-(JP18-Pad4)") (class "Default")
      (node (ref "JP18") (pin "4") (pinfunction "4_4") (pintype "passive"))
    )
    (net (code "110") (name "unconnected-(JP18-Pad5)") (class "Default")
      (node (ref "JP18") (pin "5") (pinfunction "5_5") (pintype "passive"))
    )
    (net (code "111") (name "unconnected-(JP18-Pad6)") (class "Default")
      (node (ref "JP18") (pin "6") (pinfunction "6_6") (pintype "passive"))
    )
    (net (code "112") (name "unconnected-(JP18-Pad7)") (class "Default")
      (node (ref "JP18") (pin "7") (pinfunction "7_7") (pintype "passive"))
    )
    (net (code "113") (name "unconnected-(JP18-Pad8)") (class "Default")
      (node (ref "JP18") (pin "8") (pinfunction "8_8") (pintype "passive"))
    )
    (net (code "114") (name "unconnected-(JP18-Pad9)") (class "Default")
      (node (ref "JP18") (pin "9") (pinfunction "9_9") (pintype "passive"))
    )
    (net (code "115") (name "unconnected-(JP19-Pad2)") (class "Default")
      (node (ref "JP19") (pin "2") (pinfunction "2_2") (pintype "passive"))
    )
    (net (code "116") (name "unconnected-(JP19-Pad3)") (class "Default")
      (node (ref "JP19") (pin "3") (pinfunction "3_3") (pintype "passive"))
    )
    (net (code "117") (name "unconnected-(JP19-Pad4)") (class "Default")
      (node (ref "JP19") (pin "4") (pinfunction "4_4") (pintype "passive"))
    )
    (net (code "118") (name "unconnected-(JP19-Pad5)") (class "Default")
      (node (ref "JP19") (pin "5") (pinfunction "5_5") (pintype "passive"))
    )
    (net (code "119") (name "unconnected-(JP19-Pad6)") (class "Default")
      (node (ref "JP19") (pin "6") (pinfunction "6_6") (pintype "passive"))
    )
    (net (code "120") (name "unconnected-(JP19-Pad7)") (class "Default")
      (node (ref "JP19") (pin "7") (pinfunction "7_7") (pintype "passive"))
    )
    (net (code "121") (name "unconnected-(JP19-Pad8)") (class "Default")
      (node (ref "JP19") (pin "8") (pinfunction "8_8") (pintype "passive"))
    )
    (net (code "122") (name "unconnected-(JP19-Pad9)") (class "Default")
      (node (ref "JP19") (pin "9") (pinfunction "9_9") (pintype "passive"))
    )
    (net (code "123") (name "unconnected-(JP20-Pad2)") (class "Default")
      (node (ref "JP20") (pin "2") (pinfunction "2_2") (pintype "passive"))
    )
    (net (code "124") (name "unconnected-(JP20-Pad3)") (class "Default")
      (node (ref "JP20") (pin "3") (pinfunction "3_3") (pintype "passive"))
    )
    (net (code "125") (name "unconnected-(JP20-Pad4)") (class "Default")
      (node (ref "JP20") (pin "4") (pinfunction "4_4") (pintype "passive"))
    )
    (net (code "126") (name "unconnected-(JP20-Pad5)") (class "Default")
      (node (ref "JP20") (pin "5") (pinfunction "5_5") (pintype "passive"))
    )
    (net (code "127") (name "unconnected-(JP20-Pad6)") (class "Default")
      (node (ref "JP20") (pin "6") (pinfunction "6_6") (pintype "passive"))
    )
    (net (code "128") (name "unconnected-(JP20-Pad7)") (class "Default")
      (node (ref "JP20") (pin "7") (pinfunction "7_7") (pintype "passive"))
    )
    (net (code "129") (name "unconnected-(JP20-Pad8)") (class "Default")
      (node (ref "JP20") (pin "8") (pinfunction "8_8") (pintype "passive"))
    )
    (net (code "130") (name "unconnected-(JP20-Pad9)") (class "Default")
      (node (ref "JP20") (pin "9") (pinfunction "9_9") (pintype "passive"))
    )
    (net (code "131") (name "unconnected-(JP21-Pad2)") (class "Default")
      (node (ref "JP21") (pin "2") (pinfunction "2_2") (pintype "passive"))
    )
    (net (code "132") (name "unconnected-(JP21-Pad3)") (class "Default")
      (node (ref "JP21") (pin "3") (pinfunction "3_3") (pintype "passive"))
    )
    (net (code "133") (name "unconnected-(JP21-Pad4)") (class "Default")
      (node (ref "JP21") (pin "4") (pinfunction "4_4") (pintype "passive"))
    )
    (net (code "134") (name "unconnected-(JP21-Pad5)") (class "Default")
      (node (ref "JP21") (pin "5") (pinfunction "5_5") (pintype "passive"))
    )
    (net (code "135") (name "unconnected-(JP21-Pad6)") (class "Default")
      (node (ref "JP21") (pin "6") (pinfunction "6_6") (pintype "passive"))
    )
    (net (code "136") (name "unconnected-(JP21-Pad7)") (class "Default")
      (node (ref "JP21") (pin "7") (pinfunction "7_7") (pintype "passive"))
    )
    (net (code "137") (name "unconnected-(JP21-Pad8)") (class "Default")
      (node (ref "JP21") (pin "8") (pinfunction "8_8") (pintype "passive"))
    )
    (net (code "138") (name "unconnected-(JP21-Pad9)") (class "Default")
      (node (ref "JP21") (pin "9") (pinfunction "9_9") (pintype "passive"))
    )
    (net (code "139") (name "unconnected-(JP22-Pad2)") (class "Default")
      (node (ref "JP22") (pin "2") (pinfunction "2_2") (pintype "passive"))
    )
    (net (code "140") (name "unconnected-(JP22-Pad3)") (class "Default")
      (node (ref "JP22") (pin "3") (pinfunction "3_3") (pintype "passive"))
    )
    (net (code "141") (name "unconnected-(JP22-Pad4)") (class "Default")
      (node (ref "JP22") (pin "4") (pinfunction "4_4") (pintype "passive"))
    )
    (net (code "142") (name "unconnected-(JP22-Pad5)") (class "Default")
      (node (ref "JP22") (pin "5") (pinfunction "5_5") (pintype "passive"))
    )
    (net (code "143") (name "unconnected-(JP22-Pad6)") (class "Default")
      (node (ref "JP22") (pin "6") (pinfunction "6_6") (pintype "passive"))
    )
    (net (code "144") (name "unconnected-(JP22-Pad7)") (class "Default")
      (node (ref "JP22") (pin "7") (pinfunction "7_7") (pintype "passive"))
    )
    (net (code "145") (name "unconnected-(JP22-Pad8)") (class "Default")
      (node (ref "JP22") (pin "8") (pinfunction "8_8") (pintype "passive"))
    )
    (net (code "146") (name "unconnected-(JP22-Pad9)") (class "Default")
      (node (ref "JP22") (pin "9") (pinfunction "9_9") (pintype "passive"))
    )
    (net (code "147") (name "unconnected-(JP23-Pad1)") (class "Default")
      (node (ref "JP23") (pin "1") (pinfunction "1_1") (pintype "passive"))
    )
    (net (code "148") (name "unconnected-(JP23-Pad2)") (class "Default")
      (node (ref "JP23") (pin "2") (pinfunction "2_2") (pintype "passive"))
    )
    (net (code "149") (name "unconnected-(JP23-Pad3)") (class "Default")
      (node (ref "JP23") (pin "3") (pinfunction "3_3") (pintype "passive"))
    )
    (net (code "150") (name "unconnected-(JP24-Pad1)") (class "Default")
      (node (ref "JP24") (pin "1") (pinfunction "1_1") (pintype "passive"))
    )
    (net (code "151") (name "unconnected-(JP24-Pad2)") (class "Default")
      (node (ref "JP24") (pin "2") (pinfunction "2_2") (pintype "passive"))
    )
    (net (code "152") (name "unconnected-(JP24-Pad3)") (class "Default")
      (node (ref "JP24") (pin "3") (pinfunction "3_3") (pintype "passive"))
    )
    (net (code "153") (name "unconnected-(JP25-Pad1)") (class "Default")
      (node (ref "JP25") (pin "1") (pinfunction "1_1") (pintype "passive"))
    )
    (net (code "154") (name "unconnected-(JP25-Pad2)") (class "Default")
      (node (ref "JP25") (pin "2") (pinfunction "2_2") (pintype "passive"))
    )
    (net (code "155") (name "unconnected-(JP25-Pad3)") (class "Default")
      (node (ref "JP25") (pin "3") (pinfunction "3_3") (pintype "passive"))
    )
    (net (code "156") (name "unconnected-(JP203-Pad1)") (class "Default")
      (node (ref "JP203") (pin "1") (pinfunction "1_1") (pintype "passive"))
    )
    (net (code "157") (name "unconnected-(JP203-Pad2)") (class "Default")
      (node (ref "JP203") (pin "2") (pinfunction "2_2") (pintype "passive"))
    )
    (net (code "158") (name "unconnected-(JP203-Pad3)") (class "Default")
      (node (ref "JP203") (pin "3") (pinfunction "3_3") (pintype "passive"))
    )
    (net (code "159") (name "unconnected-(JP203-Pad4)") (class "Default")
      (node (ref "JP203") (pin "4") (pinfunction "4_4") (pintype "passive"))
    )
    (net (code "160") (name "unconnected-(JP203-Pad5)") (class "Default")
      (node (ref "JP203") (pin "5") (pinfunction "5_5") (pintype "passive"))
    )
    (net (code "161") (name "unconnected-(JP203-Pad6)") (class "Default")
      (node (ref "JP203") (pin "6") (pinfunction "6_6") (pintype "passive"))
    )
    (net (code "162") (name "unconnected-(JP203-Pad7)") (class "Default")
      (node (ref "JP203") (pin "7") (pinfunction "7_7") (pintype "passive"))
    )
    (net (code "163") (name "unconnected-(JP203-Pad8)") (class "Default")
      (node (ref "JP203") (pin "8") (pinfunction "8_8") (pintype "passive"))
    )
    (net (code "164") (name "unconnected-(JP203-Pad9)") (class "Default")
      (node (ref "JP203") (pin "9") (pinfunction "9_9") (pintype "passive"))
    )
    (net (code "165") (name "unconnected-(JP203-Pad10)") (class "Default")
      (node (ref "JP203") (pin "10") (pinfunction "10_10") (pintype "passive"))
    )
    (net (code "166") (name "unconnected-(JP204-Pad1)") (class "Default")
      (node (ref "JP204") (pin "1") (pinfunction "1_1") (pintype "passive"))
    )
    (net (code "167") (name "unconnected-(JP204-Pad2)") (class "Default")
      (node (ref "JP204") (pin "2") (pinfunction "2_2") (pintype "passive"))
    )
    (net (code "168") (name "unconnected-(JP204-Pad3)") (class "Default")
      (node (ref "JP204") (pin "3") (pinfunction "3_3") (pintype "passive"))
    )
    (net (code "169") (name "unconnected-(JP204-Pad4)") (class "Default")
      (node (ref "JP204") (pin "4") (pinfunction "4_4") (pintype "passive"))
    )
    (net (code "170") (name "unconnected-(JP204-Pad5)") (class "Default")
      (node (ref "JP204") (pin "5") (pinfunction "5_5") (pintype "passive"))
    )
    (net (code "171") (name "unconnected-(JP204-Pad6)") (class "Default")
      (node (ref "JP204") (pin "6") (pinfunction "6_6") (pintype "passive"))
    )
    (net (code "172") (name "unconnected-(JP204-Pad7)") (class "Default")
      (node (ref "JP204") (pin "7") (pinfunction "7_7") (pintype "passive"))
    )
    (net (code "173") (name "unconnected-(JP204-Pad8)") (class "Default")
      (node (ref "JP204") (pin "8") (pinfunction "8_8") (pintype "passive"))
    )
    (net (code "174") (name "unconnected-(JP204-Pad9)") (class "Default")
      (node (ref "JP204") (pin "9") (pinfunction "9_9") (pintype "passive"))
    )
    (net (code "175") (name "unconnected-(JP204-Pad10)") (class "Default")
      (node (ref "JP204") (pin "10") (pinfunction "10_10") (pintype "passive"))
    )
    (net (code "176") (name "unconnected-(JP213-Pad1)") (class "Default")
      (node (ref "JP213") (pin "1") (pinfunction "1_1") (pintype "passive"))
    )
    (net (code "177") (name "unconnected-(JP213-Pad2)") (class "Default")
      (node (ref "JP213") (pin "2") (pinfunction "2_2") (pintype "passive"))
    )
    (net (code "178") (name "unconnected-(JP213-Pad3)") (class "Default")
      (node (ref "JP213") (pin "3") (pinfunction "3_3") (pintype "passive"))
    )
    (net (code "179") (name "unconnected-(JP213-Pad4)") (class "Default")
      (node (ref "JP213") (pin "4") (pinfunction "4_4") (pintype "passive"))
    )
    (net (code "180") (name "unconnected-(JP213-Pad5)") (class "Default")
      (node (ref "JP213") (pin "5") (pinfunction "5_5") (pintype "passive"))
    )
    (net (code "181") (name "unconnected-(JP213-Pad6)") (class "Default")
      (node (ref "JP213") (pin "6") (pinfunction "6_6") (pintype "passive"))
    )
    (net (code "182") (name "unconnected-(JP213-Pad7)") (class "Default")
      (node (ref "JP213") (pin "7") (pinfunction "7_7") (pintype "passive"))
    )
    (net (code "183") (name "unconnected-(JP213-Pad8)") (class "Default")
      (node (ref "JP213") (pin "8") (pinfunction "8_8") (pintype "passive"))
    )
    (net (code "184") (name "unconnected-(JP213-Pad9)") (class "Default")
      (node (ref "JP213") (pin "9") (pinfunction "9_9") (pintype "passive"))
    )
    (net (code "185") (name "unconnected-(JP213-Pad10)") (class "Default")
      (node (ref "JP213") (pin "10") (pinfunction "10_10") (pintype "passive"))
    )
    (net (code "186") (name "unconnected-(JP214-Pad1)") (class "Default")
      (node (ref "JP214") (pin "1") (pinfunction "1_1") (pintype "passive"))
    )
    (net (code "187") (name "unconnected-(JP214-Pad2)") (class "Default")
      (node (ref "JP214") (pin "2") (pinfunction "2_2") (pintype "passive"))
    )
    (net (code "188") (name "unconnected-(JP214-Pad3)") (class "Default")
      (node (ref "JP214") (pin "3") (pinfunction "3_3") (pintype "passive"))
    )
    (net (code "189") (name "unconnected-(JP214-Pad4)") (class "Default")
      (node (ref "JP214") (pin "4") (pinfunction "4_4") (pintype "passive"))
    )
    (net (code "190") (name "unconnected-(JP214-Pad5)") (class "Default")
      (node (ref "JP214") (pin "5") (pinfunction "5_5") (pintype "passive"))
    )
    (net (code "191") (name "unconnected-(JP214-Pad6)") (class "Default")
      (node (ref "JP214") (pin "6") (pinfunction "6_6") (pintype "passive"))
    )
    (net (code "192") (name "unconnected-(JP214-Pad7)") (class "Default")
      (node (ref "JP214") (pin "7") (pinfunction "7_7") (pintype "passive"))
    )
    (net (code "193") (name "unconnected-(JP214-Pad8)") (class "Default")
      (node (ref "JP214") (pin "8") (pinfunction "8_8") (pintype "passive"))
    )
    (net (code "194") (name "unconnected-(JP214-Pad9)") (class "Default")
      (node (ref "JP214") (pin "9") (pinfunction "9_9") (pintype "passive"))
    )
    (net (code "195") (name "unconnected-(JP214-Pad10)") (class "Default")
      (node (ref "JP214") (pin "10") (pinfunction "10_10") (pintype "passive"))
    )
  )
)
